# Quimera_IMU_board.net
KiCad netlist of a schematic drawn in EAGLE
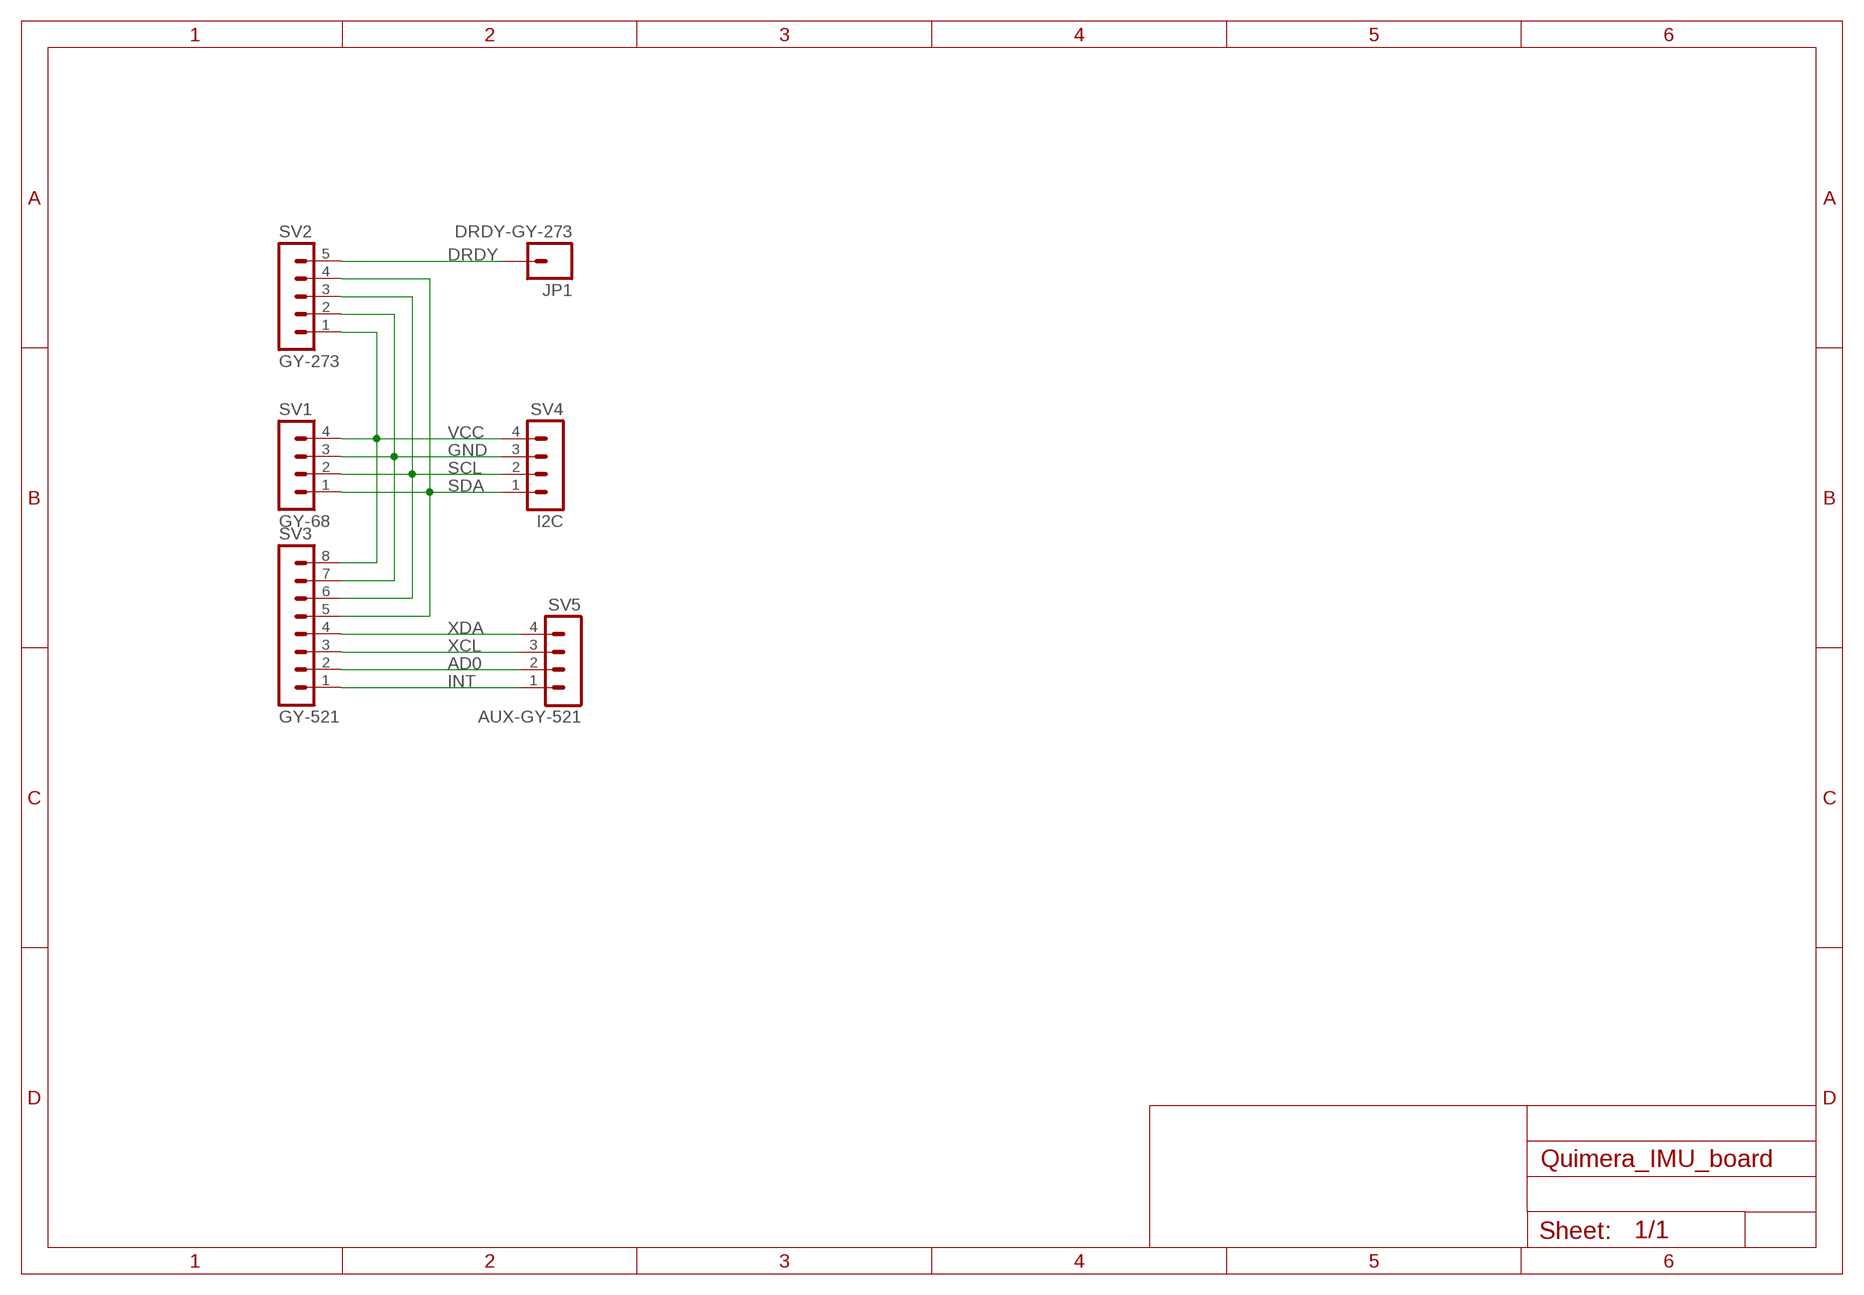
[diagram p0: schematic, sheet 1]

(export (version "E")
  (design (tool "Eeschema 10.0.6"))
  (components
    (comp (ref "JP1")
      (value "DRDY-GY-273")
      (footprint "eagle-import:1X01_OFFSET")
      (libsource (lib "eagle-import") (part "M01OFFSET"))
    )
    (comp (ref "SV1")
      (value "GY-68")
      (footprint "eagle-import:MA04-1")
      (libsource (lib "eagle-import") (part "MA04-1"))
    )
    (comp (ref "SV2")
      (value "GY-273")
      (footprint "eagle-import:MA05-1")
      (libsource (lib "eagle-import") (part "MA05-1"))
    )
    (comp (ref "SV3")
      (value "GY-521")
      (footprint "eagle-import:MA08-1")
      (libsource (lib "eagle-import") (part "MA08-1"))
    )
    (comp (ref "SV4")
      (value "I2C")
      (footprint "eagle-import:MA04-1")
      (libsource (lib "eagle-import") (part "MA04-1"))
    )
    (comp (ref "SV5")
      (value "AUX-GY-521")
      (footprint "eagle-import:MA04-1")
      (libsource (lib "eagle-import") (part "MA04-1"))
    )
  )
  (nets
    (net (code "1") (name "/AD0") (class "Default")
      (node (ref "SV3") (pin "2") (pinfunction "2_2") (pintype "passive"))
      (node (ref "SV5") (pin "2") (pinfunction "2_2") (pintype "passive"))
    )
    (net (code "2") (name "/DRDY") (class "Default")
      (node (ref "JP1") (pin "1") (pinfunction "1_1") (pintype "passive"))
      (node (ref "SV2") (pin "5") (pinfunction "5_5") (pintype "passive"))
    )
    (net (code "3") (name "/GND") (class "Default")
      (node (ref "SV1") (pin "3") (pinfunction "3_3") (pintype "passive"))
      (node (ref "SV2") (pin "2") (pinfunction "2_2") (pintype "passive"))
      (node (ref "SV3") (pin "7") (pinfunction "7_7") (pintype "passive"))
      (node (ref "SV4") (pin "3") (pinfunction "3_3") (pintype "passive"))
    )
    (net (code "4") (name "/INT") (class "Default")
      (node (ref "SV3") (pin "1") (pinfunction "1_1") (pintype "passive"))
      (node (ref "SV5") (pin "1") (pinfunction "1_1") (pintype "passive"))
    )
    (net (code "5") (name "/SCL") (class "Default")
      (node (ref "SV1") (pin "2") (pinfunction "2_2") (pintype "passive"))
      (node (ref "SV2") (pin "3") (pinfunction "3_3") (pintype "passive"))
      (node (ref "SV3") (pin "6") (pinfunction "6_6") (pintype "passive"))
      (node (ref "SV4") (pin "2") (pinfunction "2_2") (pintype "passive"))
    )
    (net (code "6") (name "/SDA") (class "Default")
      (node (ref "SV1") (pin "1") (pinfunction "1_1") (pintype "passive"))
      (node (ref "SV2") (pin "4") (pinfunction "4_4") (pintype "passive"))
      (node (ref "SV3") (pin "5") (pinfunction "5_5") (pintype "passive"))
      (node (ref "SV4") (pin "1") (pinfunction "1_1") (pintype "passive"))
    )
    (net (code "7") (name "/VCC") (class "Default")
      (node (ref "SV1") (pin "4") (pinfunction "4_4") (pintype "passive"))
      (node (ref "SV2") (pin "1") (pinfunction "1_1") (pintype "passive"))
      (node (ref "SV3") (pin "8") (pinfunction "8_8") (pintype "passive"))
      (node (ref "SV4") (pin "4") (pinfunction "4_4") (pintype "passive"))
    )
    (net (code "8") (name "/XCL") (class "Default")
      (node (ref "SV3") (pin "3") (pinfunction "3_3") (pintype "passive"))
      (node (ref "SV5") (pin "3") (pinfunction "3_3") (pintype "passive"))
    )
    (net (code "9") (name "/XDA") (class "Default")
      (node (ref "SV3") (pin "4") (pinfunction "4_4") (pintype "passive"))
      (node (ref "SV5") (pin "4") (pinfunction "4_4") (pintype "passive"))
    )
  )
)
